# RPiEvm3.net
KiCad netlist of a schematic drawn in EAGLE
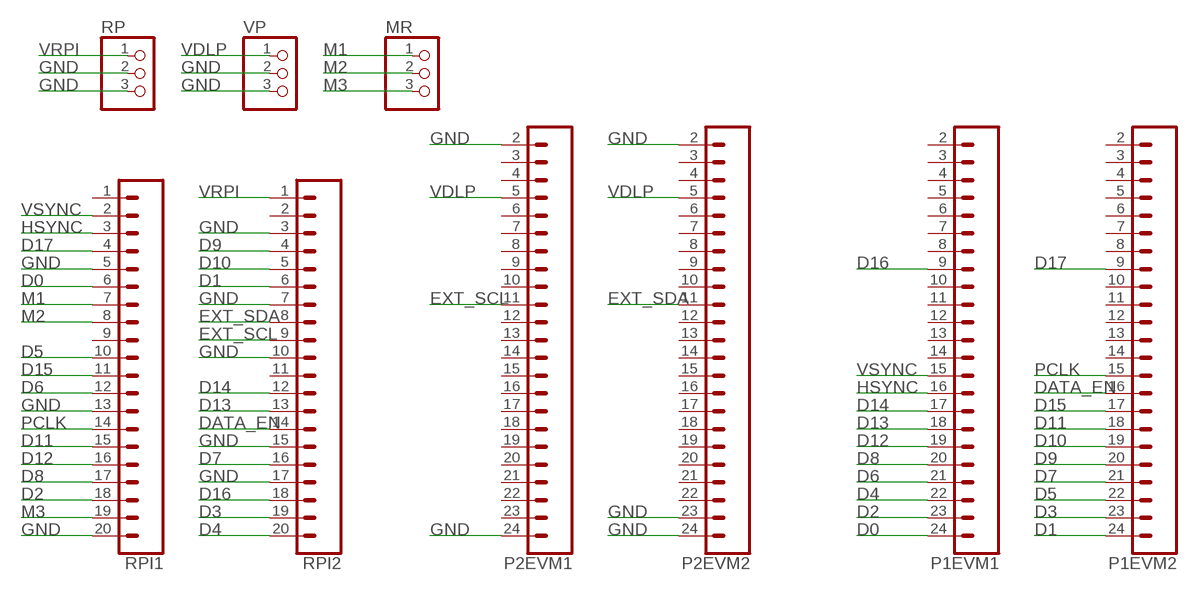
[diagram p0: schematic, sheet 1]

(export (version "E")
  (design (tool "Eeschema 10.0.6"))
  (components
    (comp (ref "MR")
      (value "PINHD-1X3")
      (footprint "eagle-import:1X03")
      (libsource (lib "eagle-import") (part "PINHD-1X3"))
    )
    (comp (ref "P1EVM1")
      (value "CONN_23")
      (footprint "eagle-import:1X23")
      (libsource (lib "eagle-import") (part "CONN_23"))
    )
    (comp (ref "P1EVM2")
      (value "CONN_23")
      (footprint "eagle-import:1X23")
      (libsource (lib "eagle-import") (part "CONN_23"))
    )
    (comp (ref "P2EVM1")
      (value "CONN_23")
      (footprint "eagle-import:1X23")
      (libsource (lib "eagle-import") (part "CONN_23"))
    )
    (comp (ref "P2EVM2")
      (value "CONN_23")
      (footprint "eagle-import:1X23")
      (libsource (lib "eagle-import") (part "CONN_23"))
    )
    (comp (ref "RP")
      (value "PINHD-1X3")
      (footprint "eagle-import:1X03")
      (libsource (lib "eagle-import") (part "adafruit_420_PINHD-1X3"))
    )
    (comp (ref "RPI1")
      (value "CONN_20")
      (footprint "eagle-import:1X20")
      (libsource (lib "eagle-import") (part "CONN_20"))
    )
    (comp (ref "RPI2")
      (value "CONN_20")
      (footprint "eagle-import:1X20")
      (libsource (lib "eagle-import") (part "CONN_20"))
    )
    (comp (ref "VP")
      (value "PINHD-1X3")
      (footprint "eagle-import:1X03")
      (libsource (lib "eagle-import") (part "PINHD-1X3"))
    )
  )
  (nets
    (net (code "1") (name "/D0") (class "Default")
      (node (ref "P1EVM1") (pin "24") (pinfunction "24_24") (pintype "passive"))
      (node (ref "RPI1") (pin "6") (pinfunction "6_6") (pintype "passive"))
    )
    (net (code "2") (name "/D1") (class "Default")
      (node (ref "P1EVM2") (pin "24") (pinfunction "24_24") (pintype "passive"))
      (node (ref "RPI2") (pin "6") (pinfunction "6_6") (pintype "passive"))
    )
    (net (code "3") (name "/D2") (class "Default")
      (node (ref "P1EVM1") (pin "23") (pinfunction "23_23") (pintype "passive"))
      (node (ref "RPI1") (pin "18") (pinfunction "18_18") (pintype "passive"))
    )
    (net (code "4") (name "/D3") (class "Default")
      (node (ref "P1EVM2") (pin "23") (pinfunction "23_23") (pintype "passive"))
      (node (ref "RPI2") (pin "19") (pinfunction "19_19") (pintype "passive"))
    )
    (net (code "5") (name "/D4") (class "Default")
      (node (ref "P1EVM1") (pin "22") (pinfunction "22_22") (pintype "passive"))
      (node (ref "RPI2") (pin "20") (pinfunction "20_20") (pintype "passive"))
    )
    (net (code "6") (name "/D5") (class "Default")
      (node (ref "P1EVM2") (pin "22") (pinfunction "22_22") (pintype "passive"))
      (node (ref "RPI1") (pin "10") (pinfunction "10_10") (pintype "passive"))
    )
    (net (code "7") (name "/D6") (class "Default")
      (node (ref "P1EVM1") (pin "21") (pinfunction "21_21") (pintype "passive"))
      (node (ref "RPI1") (pin "12") (pinfunction "12_12") (pintype "passive"))
    )
    (net (code "8") (name "/D7") (class "Default")
      (node (ref "P1EVM2") (pin "21") (pinfunction "21_21") (pintype "passive"))
      (node (ref "RPI2") (pin "16") (pinfunction "16_16") (pintype "passive"))
    )
    (net (code "9") (name "/D8") (class "Default")
      (node (ref "P1EVM1") (pin "20") (pinfunction "20_20") (pintype "passive"))
      (node (ref "RPI1") (pin "17") (pinfunction "17_17") (pintype "passive"))
    )
    (net (code "10") (name "/D9") (class "Default")
      (node (ref "P1EVM2") (pin "20") (pinfunction "20_20") (pintype "passive"))
      (node (ref "RPI2") (pin "4") (pinfunction "4_4") (pintype "passive"))
    )
    (net (code "11") (name "/D10") (class "Default")
      (node (ref "P1EVM2") (pin "19") (pinfunction "19_19") (pintype "passive"))
      (node (ref "RPI2") (pin "5") (pinfunction "5_5") (pintype "passive"))
    )
    (net (code "12") (name "/D11") (class "Default")
      (node (ref "P1EVM2") (pin "18") (pinfunction "18_18") (pintype "passive"))
      (node (ref "RPI1") (pin "15") (pinfunction "15_15") (pintype "passive"))
    )
    (net (code "13") (name "/D12") (class "Default")
      (node (ref "P1EVM1") (pin "19") (pinfunction "19_19") (pintype "passive"))
      (node (ref "RPI1") (pin "16") (pinfunction "16_16") (pintype "passive"))
    )
    (net (code "14") (name "/D13") (class "Default")
      (node (ref "P1EVM1") (pin "18") (pinfunction "18_18") (pintype "passive"))
      (node (ref "RPI2") (pin "13") (pinfunction "13_13") (pintype "passive"))
    )
    (net (code "15") (name "/D14") (class "Default")
      (node (ref "P1EVM1") (pin "17") (pinfunction "17_17") (pintype "passive"))
      (node (ref "RPI2") (pin "12") (pinfunction "12_12") (pintype "passive"))
    )
    (net (code "16") (name "/D15") (class "Default")
      (node (ref "P1EVM2") (pin "17") (pinfunction "17_17") (pintype "passive"))
      (node (ref "RPI1") (pin "11") (pinfunction "11_11") (pintype "passive"))
    )
    (net (code "17") (name "/D16") (class "Default")
      (node (ref "P1EVM1") (pin "9") (pinfunction "9_9") (pintype "passive"))
      (node (ref "RPI2") (pin "18") (pinfunction "18_18") (pintype "passive"))
    )
    (net (code "18") (name "/D17") (class "Default")
      (node (ref "P1EVM2") (pin "9") (pinfunction "9_9") (pintype "passive"))
      (node (ref "RPI1") (pin "4") (pinfunction "4_4") (pintype "passive"))
    )
    (net (code "19") (name "/DATA_EN") (class "Default")
      (node (ref "P1EVM2") (pin "16") (pinfunction "16_16") (pintype "passive"))
      (node (ref "RPI2") (pin "14") (pinfunction "14_14") (pintype "passive"))
    )
    (net (code "20") (name "/EXT_SCL") (class "Default")
      (node (ref "P2EVM1") (pin "11") (pinfunction "11_11") (pintype "passive"))
      (node (ref "RPI2") (pin "9") (pinfunction "9_9") (pintype "passive"))
    )
    (net (code "21") (name "/EXT_SDA") (class "Default")
      (node (ref "P2EVM2") (pin "11") (pinfunction "11_11") (pintype "passive"))
      (node (ref "RPI2") (pin "8") (pinfunction "8_8") (pintype "passive"))
    )
    (net (code "22") (name "/GND") (class "Default")
      (node (ref "P2EVM1") (pin "2") (pinfunction "2_2") (pintype "passive"))
      (node (ref "P2EVM1") (pin "24") (pinfunction "24_24") (pintype "passive"))
      (node (ref "P2EVM2") (pin "2") (pinfunction "2_2") (pintype "passive"))
      (node (ref "P2EVM2") (pin "23") (pinfunction "23_23") (pintype "passive"))
      (node (ref "P2EVM2") (pin "24") (pinfunction "24_24") (pintype "passive"))
      (node (ref "RP") (pin "2") (pinfunction "2_2") (pintype "passive"))
      (node (ref "RP") (pin "3") (pinfunction "3_3") (pintype "passive"))
      (node (ref "RPI1") (pin "13") (pinfunction "13_13") (pintype "passive"))
      (node (ref "RPI1") (pin "20") (pinfunction "20_20") (pintype "passive"))
      (node (ref "RPI1") (pin "5") (pinfunction "5_5") (pintype "passive"))
      (node (ref "RPI2") (pin "10") (pinfunction "10_10") (pintype "passive"))
      (node (ref "RPI2") (pin "15") (pinfunction "15_15") (pintype "passive"))
      (node (ref "RPI2") (pin "17") (pinfunction "17_17") (pintype "passive"))
      (node (ref "RPI2") (pin "3") (pinfunction "3_3") (pintype "passive"))
      (node (ref "RPI2") (pin "7") (pinfunction "7_7") (pintype "passive"))
      (node (ref "VP") (pin "2") (pinfunction "2_2") (pintype "passive"))
      (node (ref "VP") (pin "3") (pinfunction "3_3") (pintype "passive"))
    )
    (net (code "23") (name "/HSYNC") (class "Default")
      (node (ref "P1EVM1") (pin "16") (pinfunction "16_16") (pintype "passive"))
      (node (ref "RPI1") (pin "3") (pinfunction "3_3") (pintype "passive"))
    )
    (net (code "24") (name "/M1") (class "Default")
      (node (ref "MR") (pin "1") (pinfunction "1_1") (pintype "passive"))
      (node (ref "RPI1") (pin "7") (pinfunction "7_7") (pintype "passive"))
    )
    (net (code "25") (name "/M2") (class "Default")
      (node (ref "MR") (pin "2") (pinfunction "2_2") (pintype "passive"))
      (node (ref "RPI1") (pin "8") (pinfunction "8_8") (pintype "passive"))
    )
    (net (code "26") (name "/M3") (class "Default")
      (node (ref "MR") (pin "3") (pinfunction "3_3") (pintype "passive"))
      (node (ref "RPI1") (pin "19") (pinfunction "19_19") (pintype "passive"))
    )
    (net (code "27") (name "/PCLK") (class "Default")
      (node (ref "P1EVM2") (pin "15") (pinfunction "15_15") (pintype "passive"))
      (node (ref "RPI1") (pin "14") (pinfunction "14_14") (pintype "passive"))
    )
    (net (code "28") (name "/VDLP") (class "Default")
      (node (ref "P2EVM1") (pin "5") (pinfunction "5_5") (pintype "passive"))
      (node (ref "P2EVM2") (pin "5") (pinfunction "5_5") (pintype "passive"))
      (node (ref "VP") (pin "1") (pinfunction "1_1") (pintype "passive"))
    )
    (net (code "29") (name "/VRPI") (class "Default")
      (node (ref "RP") (pin "1") (pinfunction "1_1") (pintype "passive"))
      (node (ref "RPI2") (pin "1") (pinfunction "1_1") (pintype "passive"))
    )
    (net (code "30") (name "/VSYNC") (class "Default")
      (node (ref "P1EVM1") (pin "15") (pinfunction "15_15") (pintype "passive"))
      (node (ref "RPI1") (pin "2") (pinfunction "2_2") (pintype "passive"))
    )
    (net (code "31") (name "unconnected-(P1EVM1-Pad2)") (class "Default")
      (node (ref "P1EVM1") (pin "2") (pinfunction "2_2") (pintype "passive"))
    )
    (net (code "32") (name "unconnected-(P1EVM1-Pad3)") (class "Default")
      (node (ref "P1EVM1") (pin "3") (pinfunction "3_3") (pintype "passive"))
    )
    (net (code "33") (name "unconnected-(P1EVM1-Pad4)") (class "Default")
      (node (ref "P1EVM1") (pin "4") (pinfunction "4_4") (pintype "passive"))
    )
    (net (code "34") (name "unconnected-(P1EVM1-Pad5)") (class "Default")
      (node (ref "P1EVM1") (pin "5") (pinfunction "5_5") (pintype "passive"))
    )
    (net (code "35") (name "unconnected-(P1EVM1-Pad6)") (class "Default")
      (node (ref "P1EVM1") (pin "6") (pinfunction "6_6") (pintype "passive"))
    )
    (net (code "36") (name "unconnected-(P1EVM1-Pad7)") (class "Default")
      (node (ref "P1EVM1") (pin "7") (pinfunction "7_7") (pintype "passive"))
    )
    (net (code "37") (name "unconnected-(P1EVM1-Pad8)") (class "Default")
      (node (ref "P1EVM1") (pin "8") (pinfunction "8_8") (pintype "passive"))
    )
    (net (code "38") (name "unconnected-(P1EVM1-Pad10)") (class "Default")
      (node (ref "P1EVM1") (pin "10") (pinfunction "10_10") (pintype "passive"))
    )
    (net (code "39") (name "unconnected-(P1EVM1-Pad11)") (class "Default")
      (node (ref "P1EVM1") (pin "11") (pinfunction "11_11") (pintype "passive"))
    )
    (net (code "40") (name "unconnected-(P1EVM1-Pad12)") (class "Default")
      (node (ref "P1EVM1") (pin "12") (pinfunction "12_12") (pintype "passive"))
    )
    (net (code "41") (name "unconnected-(P1EVM1-Pad13)") (class "Default")
      (node (ref "P1EVM1") (pin "13") (pinfunction "13_13") (pintype "passive"))
    )
    (net (code "42") (name "unconnected-(P1EVM1-Pad14)") (class "Default")
      (node (ref "P1EVM1") (pin "14") (pinfunction "14_14") (pintype "passive"))
    )
    (net (code "43") (name "unconnected-(P1EVM2-Pad2)") (class "Default")
      (node (ref "P1EVM2") (pin "2") (pinfunction "2_2") (pintype "passive"))
    )
    (net (code "44") (name "unconnected-(P1EVM2-Pad3)") (class "Default")
      (node (ref "P1EVM2") (pin "3") (pinfunction "3_3") (pintype "passive"))
    )
    (net (code "45") (name "unconnected-(P1EVM2-Pad4)") (class "Default")
      (node (ref "P1EVM2") (pin "4") (pinfunction "4_4") (pintype "passive"))
    )
    (net (code "46") (name "unconnected-(P1EVM2-Pad5)") (class "Default")
      (node (ref "P1EVM2") (pin "5") (pinfunction "5_5") (pintype "passive"))
    )
    (net (code "47") (name "unconnected-(P1EVM2-Pad6)") (class "Default")
      (node (ref "P1EVM2") (pin "6") (pinfunction "6_6") (pintype "passive"))
    )
    (net (code "48") (name "unconnected-(P1EVM2-Pad7)") (class "Default")
      (node (ref "P1EVM2") (pin "7") (pinfunction "7_7") (pintype "passive"))
    )
    (net (code "49") (name "unconnected-(P1EVM2-Pad8)") (class "Default")
      (node (ref "P1EVM2") (pin "8") (pinfunction "8_8") (pintype "passive"))
    )
    (net (code "50") (name "unconnected-(P1EVM2-Pad10)") (class "Default")
      (node (ref "P1EVM2") (pin "10") (pinfunction "10_10") (pintype "passive"))
    )
    (net (code "51") (name "unconnected-(P1EVM2-Pad11)") (class "Default")
      (node (ref "P1EVM2") (pin "11") (pinfunction "11_11") (pintype "passive"))
    )
    (net (code "52") (name "unconnected-(P1EVM2-Pad12)") (class "Default")
      (node (ref "P1EVM2") (pin "12") (pinfunction "12_12") (pintype "passive"))
    )
    (net (code "53") (name "unconnected-(P1EVM2-Pad13)") (class "Default")
      (node (ref "P1EVM2") (pin "13") (pinfunction "13_13") (pintype "passive"))
    )
    (net (code "54") (name "unconnected-(P1EVM2-Pad14)") (class "Default")
      (node (ref "P1EVM2") (pin "14") (pinfunction "14_14") (pintype "passive"))
    )
    (net (code "55") (name "unconnected-(P2EVM1-Pad3)") (class "Default")
      (node (ref "P2EVM1") (pin "3") (pinfunction "3_3") (pintype "passive"))
    )
    (net (code "56") (name "unconnected-(P2EVM1-Pad4)") (class "Default")
      (node (ref "P2EVM1") (pin "4") (pinfunction "4_4") (pintype "passive"))
    )
    (net (code "57") (name "unconnected-(P2EVM1-Pad6)") (class "Default")
      (node (ref "P2EVM1") (pin "6") (pinfunction "6_6") (pintype "passive"))
    )
    (net (code "58") (name "unconnected-(P2EVM1-Pad7)") (class "Default")
      (node (ref "P2EVM1") (pin "7") (pinfunction "7_7") (pintype "passive"))
    )
    (net (code "59") (name "unconnected-(P2EVM1-Pad8)") (class "Default")
      (node (ref "P2EVM1") (pin "8") (pinfunction "8_8") (pintype "passive"))
    )
    (net (code "60") (name "unconnected-(P2EVM1-Pad9)") (class "Default")
      (node (ref "P2EVM1") (pin "9") (pinfunction "9_9") (pintype "passive"))
    )
    (net (code "61") (name "unconnected-(P2EVM1-Pad10)") (class "Default")
      (node (ref "P2EVM1") (pin "10") (pinfunction "10_10") (pintype "passive"))
    )
    (net (code "62") (name "unconnected-(P2EVM1-Pad12)") (class "Default")
      (node (ref "P2EVM1") (pin "12") (pinfunction "12_12") (pintype "passive"))
    )
    (net (code "63") (name "unconnected-(P2EVM1-Pad13)") (class "Default")
      (node (ref "P2EVM1") (pin "13") (pinfunction "13_13") (pintype "passive"))
    )
    (net (code "64") (name "unconnected-(P2EVM1-Pad14)") (class "Default")
      (node (ref "P2EVM1") (pin "14") (pinfunction "14_14") (pintype "passive"))
    )
    (net (code "65") (name "unconnected-(P2EVM1-Pad15)") (class "Default")
      (node (ref "P2EVM1") (pin "15") (pinfunction "15_15") (pintype "passive"))
    )
    (net (code "66") (name "unconnected-(P2EVM1-Pad16)") (class "Default")
      (node (ref "P2EVM1") (pin "16") (pinfunction "16_16") (pintype "passive"))
    )
    (net (code "67") (name "unconnected-(P2EVM1-Pad17)") (class "Default")
      (node (ref "P2EVM1") (pin "17") (pinfunction "17_17") (pintype "passive"))
    )
    (net (code "68") (name "unconnected-(P2EVM1-Pad18)") (class "Default")
      (node (ref "P2EVM1") (pin "18") (pinfunction "18_18") (pintype "passive"))
    )
    (net (code "69") (name "unconnected-(P2EVM1-Pad19)") (class "Default")
      (node (ref "P2EVM1") (pin "19") (pinfunction "19_19") (pintype "passive"))
    )
    (net (code "70") (name "unconnected-(P2EVM1-Pad20)") (class "Default")
      (node (ref "P2EVM1") (pin "20") (pinfunction "20_20") (pintype "passive"))
    )
    (net (code "71") (name "unconnected-(P2EVM1-Pad21)") (class "Default")
      (node (ref "P2EVM1") (pin "21") (pinfunction "21_21") (pintype "passive"))
    )
    (net (code "72") (name "unconnected-(P2EVM1-Pad22)") (class "Default")
      (node (ref "P2EVM1") (pin "22") (pinfunction "22_22") (pintype "passive"))
    )
    (net (code "73") (name "unconnected-(P2EVM1-Pad23)") (class "Default")
      (node (ref "P2EVM1") (pin "23") (pinfunction "23_23") (pintype "passive"))
    )
    (net (code "74") (name "unconnected-(P2EVM2-Pad3)") (class "Default")
      (node (ref "P2EVM2") (pin "3") (pinfunction "3_3") (pintype "passive"))
    )
    (net (code "75") (name "unconnected-(P2EVM2-Pad4)") (class "Default")
      (node (ref "P2EVM2") (pin "4") (pinfunction "4_4") (pintype "passive"))
    )
    (net (code "76") (name "unconnected-(P2EVM2-Pad6)") (class "Default")
      (node (ref "P2EVM2") (pin "6") (pinfunction "6_6") (pintype "passive"))
    )
    (net (code "77") (name "unconnected-(P2EVM2-Pad7)") (class "Default")
      (node (ref "P2EVM2") (pin "7") (pinfunction "7_7") (pintype "passive"))
    )
    (net (code "78") (name "unconnected-(P2EVM2-Pad8)") (class "Default")
      (node (ref "P2EVM2") (pin "8") (pinfunction "8_8") (pintype "passive"))
    )
    (net (code "79") (name "unconnected-(P2EVM2-Pad9)") (class "Default")
      (node (ref "P2EVM2") (pin "9") (pinfunction "9_9") (pintype "passive"))
    )
    (net (code "80") (name "unconnected-(P2EVM2-Pad10)") (class "Default")
      (node (ref "P2EVM2") (pin "10") (pinfunction "10_10") (pintype "passive"))
    )
    (net (code "81") (name "unconnected-(P2EVM2-Pad12)") (class "Default")
      (node (ref "P2EVM2") (pin "12") (pinfunction "12_12") (pintype "passive"))
    )
    (net (code "82") (name "unconnected-(P2EVM2-Pad13)") (class "Default")
      (node (ref "P2EVM2") (pin "13") (pinfunction "13_13") (pintype "passive"))
    )
    (net (code "83") (name "unconnected-(P2EVM2-Pad14)") (class "Default")
      (node (ref "P2EVM2") (pin "14") (pinfunction "14_14") (pintype "passive"))
    )
    (net (code "84") (name "unconnected-(P2EVM2-Pad15)") (class "Default")
      (node (ref "P2EVM2") (pin "15") (pinfunction "15_15") (pintype "passive"))
    )
    (net (code "85") (name "unconnected-(P2EVM2-Pad16)") (class "Default")
      (node (ref "P2EVM2") (pin "16") (pinfunction "16_16") (pintype "passive"))
    )
    (net (code "86") (name "unconnected-(P2EVM2-Pad17)") (class "Default")
      (node (ref "P2EVM2") (pin "17") (pinfunction "17_17") (pintype "passive"))
    )
    (net (code "87") (name "unconnected-(P2EVM2-Pad18)") (class "Default")
      (node (ref "P2EVM2") (pin "18") (pinfunction "18_18") (pintype "passive"))
    )
    (net (code "88") (name "unconnected-(P2EVM2-Pad19)") (class "Default")
      (node (ref "P2EVM2") (pin "19") (pinfunction "19_19") (pintype "passive"))
    )
    (net (code "89") (name "unconnected-(P2EVM2-Pad20)") (class "Default")
      (node (ref "P2EVM2") (pin "20") (pinfunction "20_20") (pintype "passive"))
    )
    (net (code "90") (name "unconnected-(P2EVM2-Pad21)") (class "Default")
      (node (ref "P2EVM2") (pin "21") (pinfunction "21_21") (pintype "passive"))
    )
    (net (code "91") (name "unconnected-(P2EVM2-Pad22)") (class "Default")
      (node (ref "P2EVM2") (pin "22") (pinfunction "22_22") (pintype "passive"))
    )
    (net (code "92") (name "unconnected-(RPI1-Pad1)") (class "Default")
      (node (ref "RPI1") (pin "1") (pinfunction "1_1") (pintype "passive"))
    )
    (net (code "93") (name "unconnected-(RPI1-Pad9)") (class "Default")
      (node (ref "RPI1") (pin "9") (pinfunction "9_9") (pintype "passive"))
    )
    (net (code "94") (name "unconnected-(RPI2-Pad2)") (class "Default")
      (node (ref "RPI2") (pin "2") (pinfunction "2_2") (pintype "passive"))
    )
    (net (code "95") (name "unconnected-(RPI2-Pad11)") (class "Default")
      (node (ref "RPI2") (pin "11") (pinfunction "11_11") (pintype "passive"))
    )
  )
)
